# Lora-Breakout-SMD.net
KiCad netlist of a schematic drawn in EAGLE
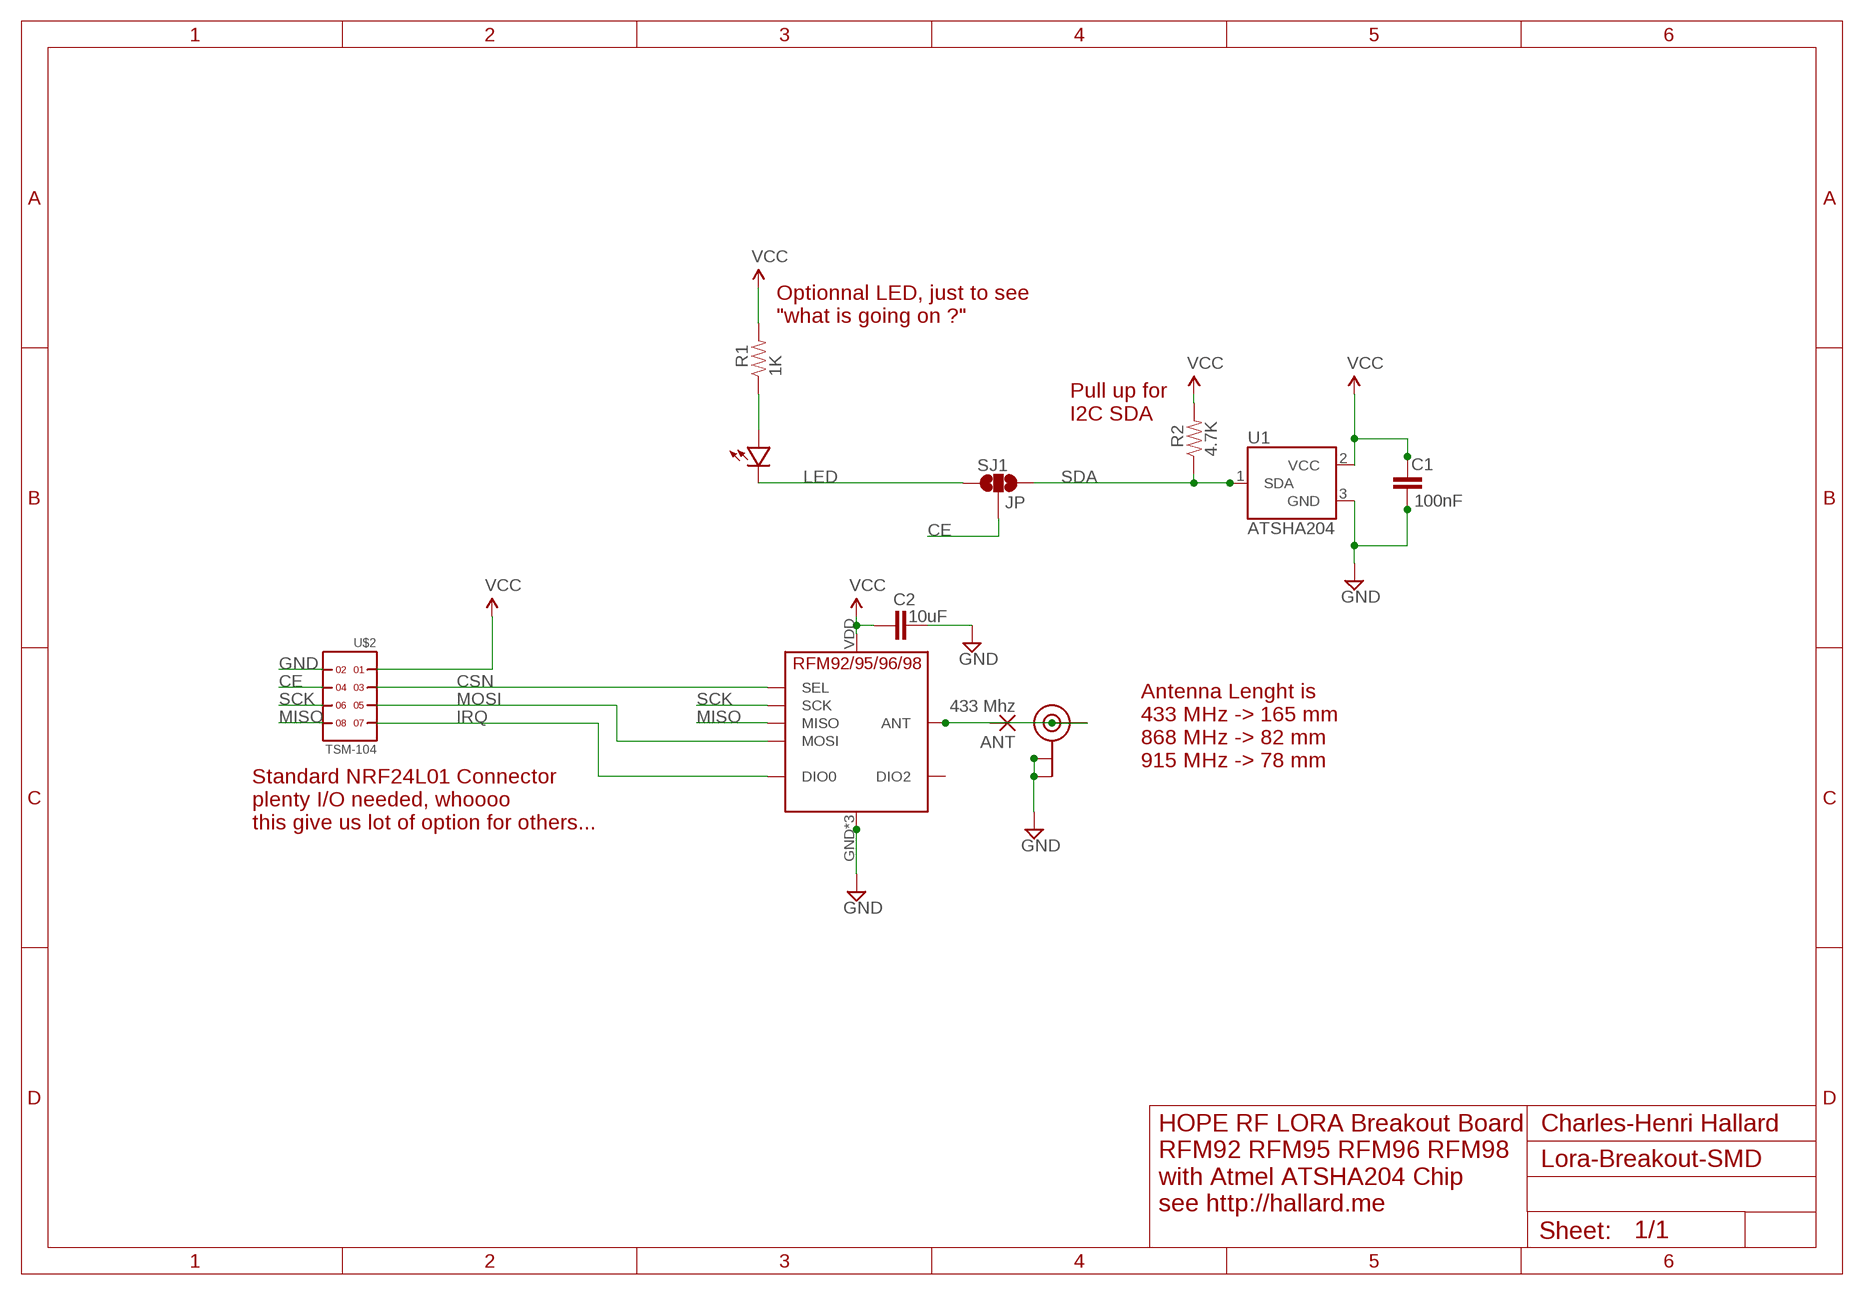
[diagram p0: schematic, sheet 1]

(export (version "E")
  (design (tool "Eeschema 10.0.6"))
  (components
    (comp (ref "ANT")
      (value "433 Mhz")
      (footprint "eagle-import:1,6_0,8")
      (libsource (lib "eagle-import") (part "1,6/0,8"))
    )
    (comp (ref "C1")
      (value "100nF")
      (footprint "eagle-import:0805-CAP")
      (libsource (lib "eagle-import") (part "CAP0805-CAP"))
    )
    (comp (ref "C2")
      (value "10uF")
      (footprint "eagle-import:0805-CAP")
      (libsource (lib "eagle-import") (part "CAP0805-CAP"))
    )
    (comp (ref "R1")
      (value "1K")
      (footprint "eagle-import:0805-RES")
      (libsource (lib "eagle-import") (part "RESISTOR0805-RES"))
    )
    (comp (ref "R2")
      (value "4.7K")
      (footprint "eagle-import:0805-RES")
      (libsource (lib "eagle-import") (part "RESISTOR0805-RES"))
    )
    (comp (ref "SJ1")
      (value "JP")
      (footprint "eagle-import:PAD-JUMPER-3-NO_YES_SILK")
      (libsource (lib "eagle-import") (part "JUMPER-PAD-3-NOYES_SILK"))
    )
    (comp (ref "U$1")
      (value "LED0805-LARGE")
      (footprint "eagle-import:0805-LED-LARGEPADS")
      (libsource (lib "eagle-import") (part "LED0805-LARGE"))
    )
    (comp (ref "U$2")
      (value "TSM-104")
      (footprint "eagle-import:TSM-104")
      (libsource (lib "eagle-import") (part "TSM-104"))
    )
    (comp (ref "U$3")
      (value "RFM95")
      (footprint "eagle-import:RFM95")
      (libsource (lib "eagle-import") (part "RFM95"))
    )
    (comp (ref "U-FL")
      (value "U.FL")
      (footprint "eagle-import:U.FL")
      (libsource (lib "eagle-import") (part "U.FL"))
    )
    (comp (ref "U1")
      (value "ATSHA204")
      (footprint "eagle-import:SOT23-3")
      (libsource (lib "eagle-import") (part "ATSHA204-TSU"))
    )
  )
  (nets
    (net (code "1") (name "/CE") (class "Default")
      (node (ref "SJ1") (pin "2") (pinfunction "2_2") (pintype "passive"))
      (node (ref "U$2") (pin "4") (pinfunction "4_4") (pintype "bidirectional"))
    )
    (net (code "2") (name "/CSN") (class "Default")
      (node (ref "U$2") (pin "3") (pinfunction "3_3") (pintype "bidirectional"))
      (node (ref "U$3") (pin "NSS") (pinfunction "SEL_NSS") (pintype "input"))
    )
    (net (code "3") (name "/IRQ") (class "Default")
      (node (ref "U$2") (pin "7") (pinfunction "7_7") (pintype "bidirectional"))
      (node (ref "U$3") (pin "DIO0") (pinfunction "DIO0_DIO0") (pintype "open_collector"))
    )
    (net (code "4") (name "/LED") (class "Default")
      (node (ref "SJ1") (pin "1") (pinfunction "1_1") (pintype "passive"))
      (node (ref "U$1") (pin "MINUS") (pinfunction "MINUS_MINUS") (pintype "passive"))
    )
    (net (code "5") (name "/MISO") (class "Default")
      (node (ref "U$2") (pin "8") (pinfunction "8_8") (pintype "bidirectional"))
      (node (ref "U$3") (pin "MISO") (pinfunction "MISO_MISO") (pintype "input"))
    )
    (net (code "6") (name "/MOSI") (class "Default")
      (node (ref "U$2") (pin "5") (pinfunction "5_5") (pintype "bidirectional"))
      (node (ref "U$3") (pin "MOSI") (pinfunction "MOSI_MOSI") (pintype "output"))
    )
    (net (code "7") (name "/SCK") (class "Default")
      (node (ref "U$2") (pin "6") (pinfunction "6_6") (pintype "bidirectional"))
      (node (ref "U$3") (pin "SCK") (pinfunction "SCK_SCK") (pintype "input"))
    )
    (net (code "8") (name "/SDA") (class "Default")
      (node (ref "R2") (pin "1") (pinfunction "1_1") (pintype "passive"))
      (node (ref "SJ1") (pin "3") (pinfunction "3_3") (pintype "passive"))
      (node (ref "U1") (pin "1") (pinfunction "SDA_1") (pintype "bidirectional"))
    )
    (net (code "9") (name "GND") (class "Default")
      (node (ref "C1") (pin "2") (pinfunction "2_2") (pintype "passive"))
      (node (ref "C2") (pin "2") (pinfunction "2_2") (pintype "passive"))
      (node (ref "U$2") (pin "2") (pinfunction "2_2") (pintype "bidirectional"))
      (node (ref "U$3") (pin "GND") (pinfunction "GND_GND") (pintype "power_in"))
      (node (ref "U$3") (pin "GND1") (pinfunction "GND_GND1") (pintype "power_in"))
      (node (ref "U$3") (pin "GND2") (pinfunction "GND_GND2") (pintype "power_in"))
      (node (ref "U-FL") (pin "1") (pinfunction "GND_1") (pintype "passive"))
      (node (ref "U-FL") (pin "2") (pinfunction "GND_2") (pintype "passive"))
      (node (ref "U1") (pin "3") (pinfunction "GND_3") (pintype "bidirectional"))
    )
    (net (code "10") (name "Net-(ANT-P)") (class "Default")
      (node (ref "ANT") (pin "1") (pinfunction "P_1") (pintype "passive"))
      (node (ref "U$3") (pin "ANT") (pinfunction "ANT_ANT") (pintype "passive"))
      (node (ref "U-FL") (pin "3") (pinfunction "SIGNAL_3") (pintype "passive"))
    )
    (net (code "11") (name "Net-(R1-Pad1)") (class "Default")
      (node (ref "R1") (pin "1") (pinfunction "1_1") (pintype "passive"))
      (node (ref "U$1") (pin "PLUS") (pinfunction "PLUS_PLUS") (pintype "passive"))
    )
    (net (code "12") (name "VCC") (class "Default")
      (node (ref "C1") (pin "1") (pinfunction "1_1") (pintype "passive"))
      (node (ref "C2") (pin "1") (pinfunction "1_1") (pintype "passive"))
      (node (ref "R1") (pin "2") (pinfunction "2_2") (pintype "passive"))
      (node (ref "R2") (pin "2") (pinfunction "2_2") (pintype "passive"))
      (node (ref "U$2") (pin "1") (pinfunction "1_1") (pintype "bidirectional"))
      (node (ref "U$3") (pin "VDD") (pinfunction "VCC_VDD") (pintype "power_in"))
      (node (ref "U1") (pin "2") (pinfunction "VCC_2") (pintype "bidirectional"))
    )
    (net (code "13") (name "unconnected-(U$3-PadDIO2)") (class "Default")
      (node (ref "U$3") (pin "DIO2") (pinfunction "DIO2_DIO2") (pintype "open_collector"))
    )
  )
)
